# ClapSwitch.net
KiCad netlist of a schematic drawn in EAGLE
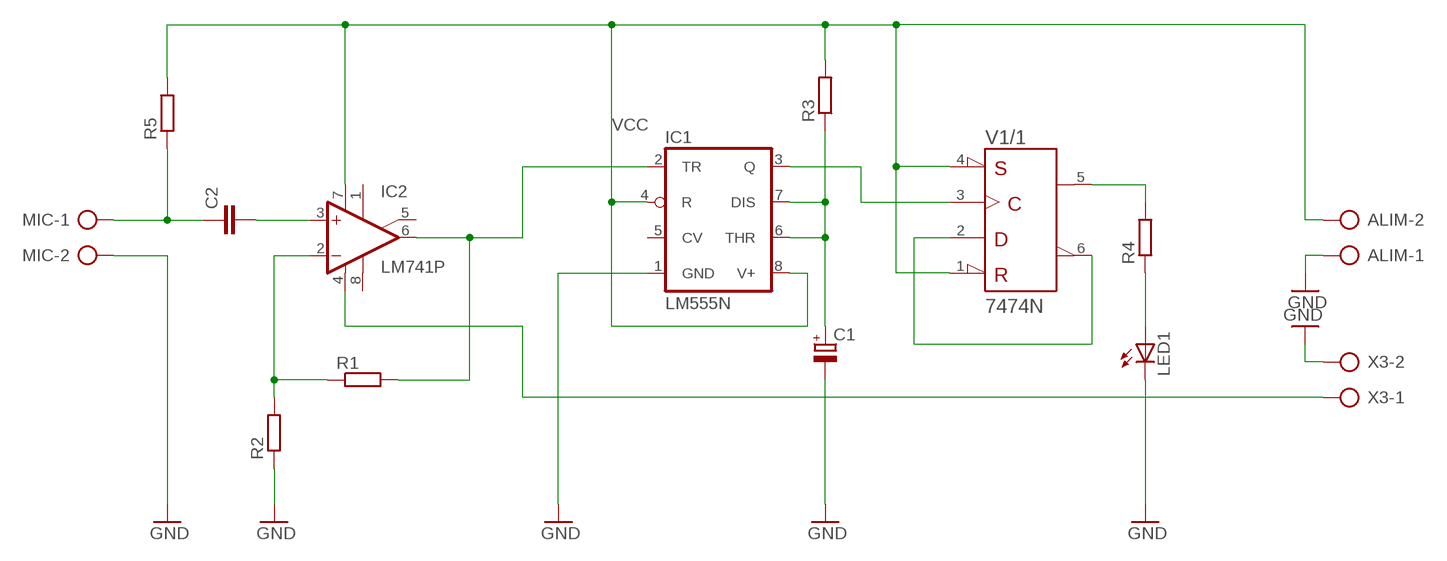
[diagram p0: schematic, sheet 1]

(export (version "E")
  (design (tool "Eeschema 10.0.6"))
  (components
    (comp (ref "ALIM")
      (value "AK300/2")
      (footprint "eagle-import:AK300_2")
      (libsource (lib "eagle-import") (part "AK300/2"))
    )
    (comp (ref "C1")
      (value "CPOL-EUE5-8.5")
      (footprint "eagle-import:E5-8,5")
      (libsource (lib "eagle-import") (part "CPOL-EUE5-8.5"))
    )
    (comp (ref "C2")
      (value "C-EU050-030X075")
      (footprint "eagle-import:C050-030X075")
      (libsource (lib "eagle-import") (part "C-EU050-030X075"))
    )
    (comp (ref "IC1")
      (value "LM555N")
      (footprint "eagle-import:DIL08")
      (libsource (lib "eagle-import") (part "555NLM"))
    )
    (comp (ref "IC2")
      (value "LM741P")
      (footprint "eagle-import:DIL08")
      (libsource (lib "eagle-import") (part "741PLM"))
    )
    (comp (ref "LED1")
      (value "LEDLZR181")
      (footprint "eagle-import:LZR181")
      (libsource (lib "eagle-import") (part "LEDLZR181"))
    )
    (comp (ref "MIC")
      (value "AK300/2")
      (footprint "eagle-import:AK300_2")
      (libsource (lib "eagle-import") (part "AK300/2"))
    )
    (comp (ref "R1")
      (value "R-EU_0204/7")
      (footprint "eagle-import:0204_7")
      (libsource (lib "eagle-import") (part "R-EU_0204/7"))
    )
    (comp (ref "R2")
      (value "R-EU_0204/7")
      (footprint "eagle-import:0204_7")
      (libsource (lib "eagle-import") (part "R-EU_0204/7"))
    )
    (comp (ref "R3")
      (value "R-EU_0204/7")
      (footprint "eagle-import:0204_7")
      (libsource (lib "eagle-import") (part "R-EU_0204/7"))
    )
    (comp (ref "R4")
      (value "R-EU_0204/7")
      (footprint "eagle-import:0204_7")
      (libsource (lib "eagle-import") (part "R-EU_0204/7"))
    )
    (comp (ref "R5")
      (value "R-EU_0204/7")
      (footprint "eagle-import:0204_7")
      (libsource (lib "eagle-import") (part "R-EU_0204/7"))
    )
    (comp (ref "V1")
      (value "7474N")
      (footprint "eagle-import:DIL14")
      (libsource (lib "eagle-import") (part "7474N"))
    )
    (comp (ref "X3")
      (value "AK300/2")
      (footprint "eagle-import:AK300_2")
      (libsource (lib "eagle-import") (part "AK300/2"))
    )
  )
  (nets
    (net (code "1") (name "/VCC") (class "Default")
      (node (ref "ALIM") (pin "2") (pinfunction "KL_2") (pintype "passive"))
      (node (ref "IC1") (pin "4") (pinfunction "R_4") (pintype "input"))
      (node (ref "IC1") (pin "8") (pinfunction "V+_8") (pintype "power_in"))
      (node (ref "IC2") (pin "7") (pinfunction "V+_7") (pintype "power_in"))
      (node (ref "R3") (pin "2") (pinfunction "2_2") (pintype "passive"))
      (node (ref "R5") (pin "2") (pinfunction "2_2") (pintype "passive"))
      (node (ref "V1") (pin "1") (pinfunction "~{CLR}_1") (pintype "input"))
      (node (ref "V1") (pin "4") (pinfunction "~{PRE}_4") (pintype "input"))
    )
    (net (code "2") (name "GND") (class "Default")
      (node (ref "ALIM") (pin "1") (pinfunction "KL_1") (pintype "passive"))
      (node (ref "C1") (pin "-") (pinfunction "-_-") (pintype "passive"))
      (node (ref "IC1") (pin "1") (pinfunction "GND_1") (pintype "power_in"))
      (node (ref "LED1") (pin "K") (pinfunction "C_K") (pintype "passive"))
      (node (ref "MIC") (pin "2") (pinfunction "KL_2") (pintype "passive"))
      (node (ref "R2") (pin "1") (pinfunction "1_1") (pintype "passive"))
      (node (ref "X3") (pin "2") (pinfunction "KL_2") (pintype "passive"))
    )
    (net (code "3") (name "Net-(IC1-DIS)") (class "Default")
      (node (ref "C1") (pin "+") (pinfunction "+_+") (pintype "passive"))
      (node (ref "IC1") (pin "6") (pinfunction "THR_6") (pintype "input"))
      (node (ref "IC1") (pin "7") (pinfunction "DIS_7") (pintype "input"))
      (node (ref "R3") (pin "1") (pinfunction "1_1") (pintype "passive"))
    )
    (net (code "4") (name "Net-(IC1-Q)") (class "Default")
      (node (ref "IC1") (pin "3") (pinfunction "Q_3") (pintype "output"))
      (node (ref "V1") (pin "3") (pinfunction "CLK_3") (pintype "input"))
    )
    (net (code "5") (name "Net-(IC1-TR)") (class "Default")
      (node (ref "IC1") (pin "2") (pinfunction "TR_2") (pintype "input"))
      (node (ref "IC2") (pin "6") (pinfunction "OUT_6") (pintype "output"))
      (node (ref "R1") (pin "2") (pinfunction "2_2") (pintype "passive"))
    )
    (net (code "6") (name "Net-(IC2-+IN)") (class "Default")
      (node (ref "C2") (pin "2") (pinfunction "2_2") (pintype "passive"))
      (node (ref "IC2") (pin "3") (pinfunction "+IN_3") (pintype "input"))
    )
    (net (code "7") (name "Net-(IC2--IN)") (class "Default")
      (node (ref "IC2") (pin "2") (pinfunction "-IN_2") (pintype "input"))
      (node (ref "R1") (pin "1") (pinfunction "1_1") (pintype "passive"))
      (node (ref "R2") (pin "2") (pinfunction "2_2") (pintype "passive"))
    )
    (net (code "8") (name "Net-(IC2-V-)") (class "Default")
      (node (ref "IC2") (pin "4") (pinfunction "V-_4") (pintype "power_in"))
      (node (ref "X3") (pin "1") (pinfunction "KL_1") (pintype "passive"))
    )
    (net (code "9") (name "Net-(LED1-PadA)") (class "Default")
      (node (ref "LED1") (pin "A") (pinfunction "A_A") (pintype "passive"))
      (node (ref "R4") (pin "1") (pinfunction "1_1") (pintype "passive"))
    )
    (net (code "10") (name "Net-(MICA-KL)") (class "Default")
      (node (ref "C2") (pin "1") (pinfunction "1_1") (pintype "passive"))
      (node (ref "MIC") (pin "1") (pinfunction "KL_1") (pintype "passive"))
      (node (ref "R5") (pin "1") (pinfunction "1_1") (pintype "passive"))
    )
    (net (code "11") (name "Net-(V1C-D)") (class "Default")
      (node (ref "V1") (pin "2") (pinfunction "D_2") (pintype "input"))
      (node (ref "V1") (pin "6") (pinfunction "~{Q}_6") (pintype "output"))
    )
    (net (code "12") (name "Net-(V1C-Q)") (class "Default")
      (node (ref "R4") (pin "2") (pinfunction "2_2") (pintype "passive"))
      (node (ref "V1") (pin "5") (pinfunction "Q_5") (pintype "output"))
    )
    (net (code "13") (name "unconnected-(IC1-CV-Pad5)") (class "Default")
      (node (ref "IC1") (pin "5") (pinfunction "CV_5") (pintype "input"))
    )
    (net (code "14") (name "unconnected-(IC2-ON1-Pad1)") (class "Default")
      (node (ref "IC2") (pin "1") (pinfunction "ON1_1") (pintype "passive"))
    )
    (net (code "15") (name "unconnected-(IC2-ON2-Pad5)") (class "Default")
      (node (ref "IC2") (pin "5") (pinfunction "ON2_5") (pintype "passive"))
    )
    (net (code "16") (name "unconnected-(IC2-OPT-Pad8)") (class "Default")
      (node (ref "IC2") (pin "8") (pinfunction "OPT_8") (pintype "passive"))
    )
  )
)
